# daclock-2_1.net
KiCad netlist of a schematic drawn in EAGLE
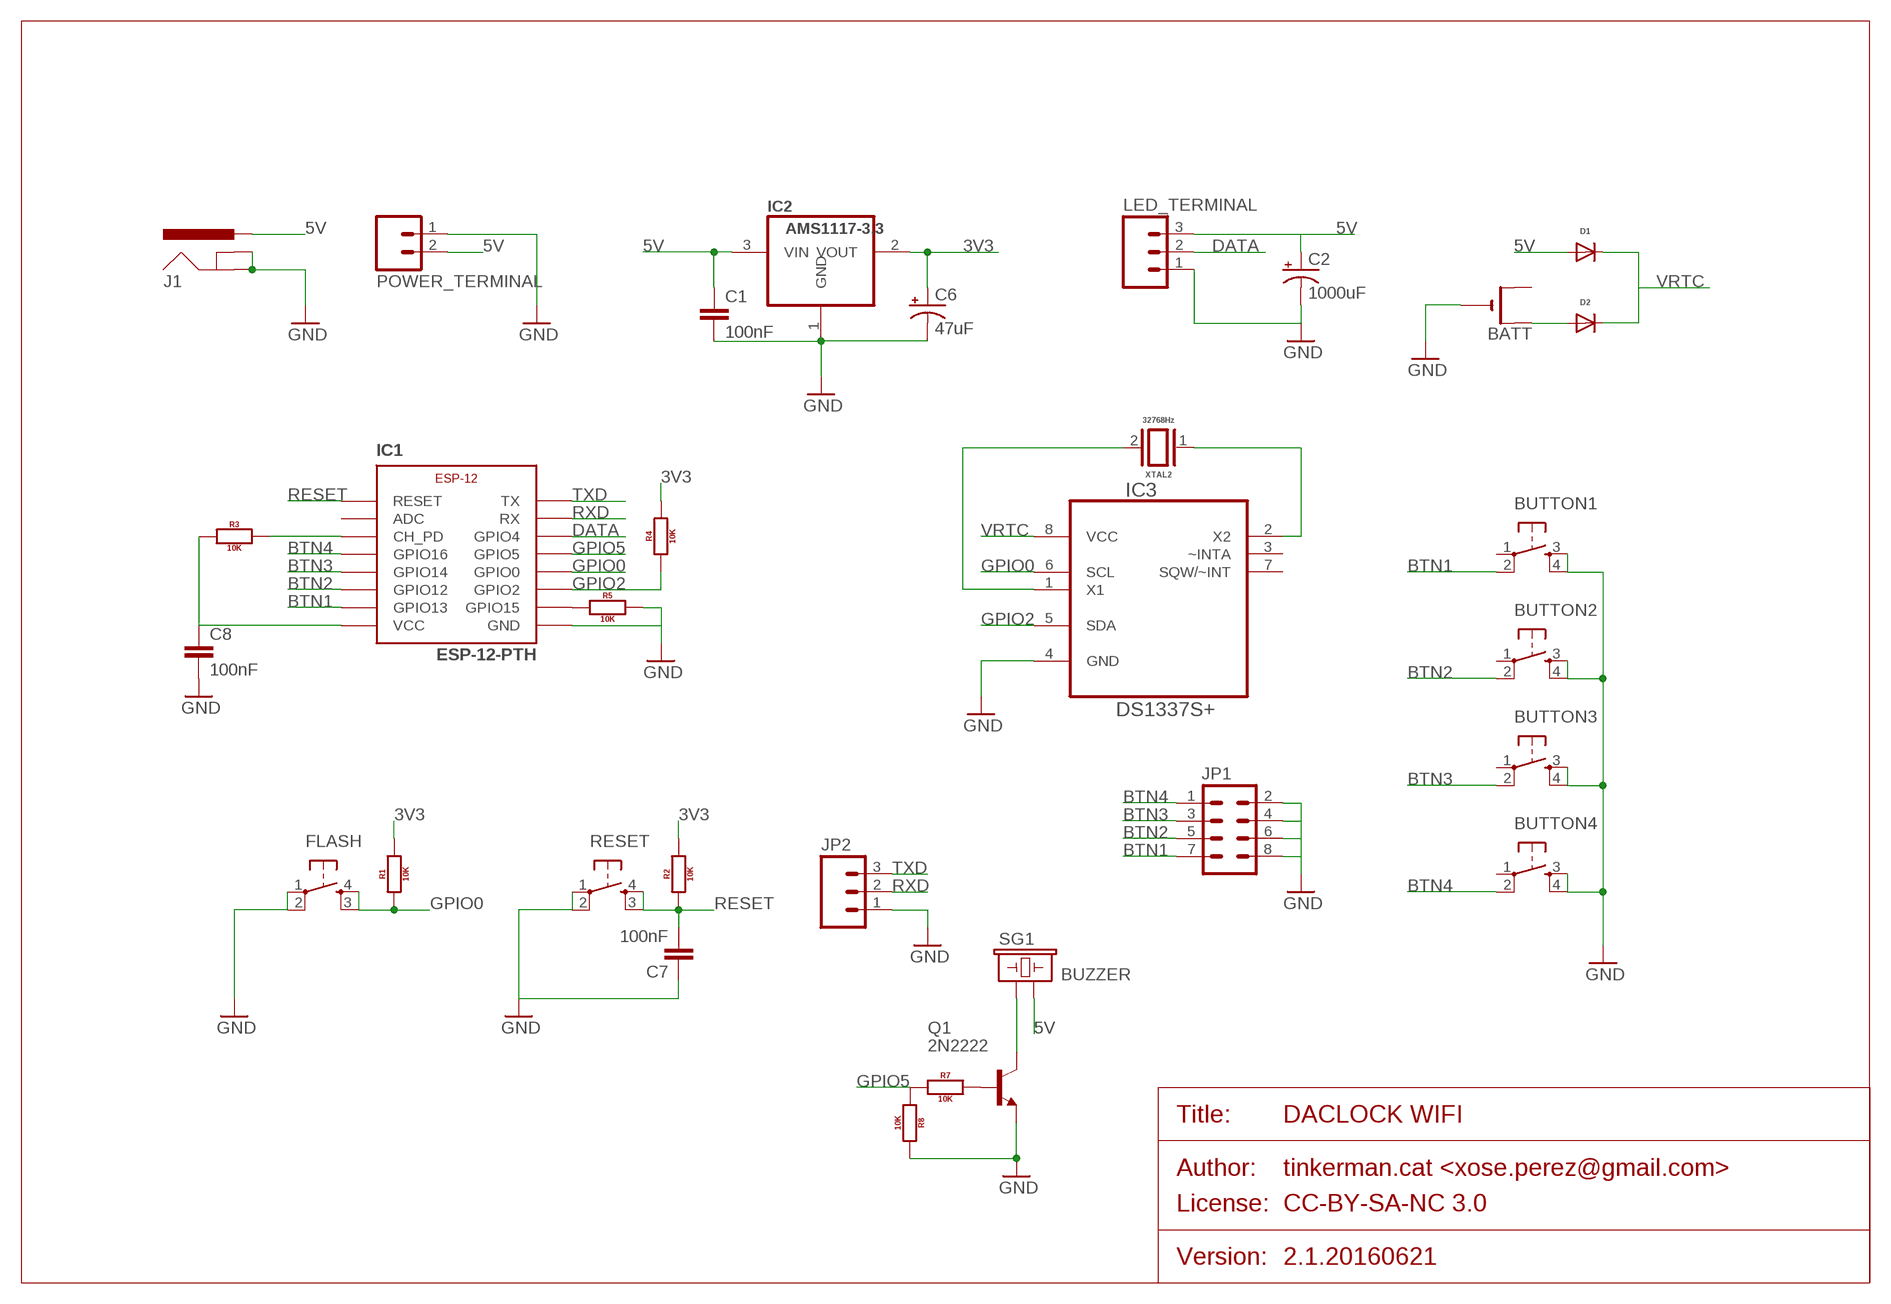
[diagram p0: schematic, sheet 1]

(export (version "E")
  (design (tool "Eeschema 10.0.6"))
  (components
    (comp (ref "BATT")
      (value "CR2032SMT")
      (footprint "eagle-import:CR2032-SMD")
      (libsource (lib "eagle-import") (part "CR2032SMT"))
    )
    (comp (ref "BUTTON1")
      (value "BTN1")
      (footprint "eagle-import:TACTILE-BUTTON")
      (libsource (lib "eagle-import") (part "TACTILE_BUTTON_PTH"))
    )
    (comp (ref "BUTTON2")
      (value "BTN2")
      (footprint "eagle-import:TACTILE-BUTTON")
      (libsource (lib "eagle-import") (part "TACTILE_BUTTON_PTH"))
    )
    (comp (ref "BUTTON3")
      (value "BTN3")
      (footprint "eagle-import:TACTILE-BUTTON")
      (libsource (lib "eagle-import") (part "TACTILE_BUTTON_PTH"))
    )
    (comp (ref "BUTTON4")
      (value "BTN4")
      (footprint "eagle-import:TACTILE-BUTTON")
      (libsource (lib "eagle-import") (part "TACTILE_BUTTON_PTH"))
    )
    (comp (ref "C1")
      (value "100nF")
      (footprint "eagle-import:C050-025X075")
      (libsource (lib "eagle-import") (part "C-EU050-025X075"))
    )
    (comp (ref "C2")
      (value "1000uF")
      (footprint "eagle-import:PANASONIC_G")
      (libsource (lib "eagle-import") (part "CAP_POLG"))
    )
    (comp (ref "C6")
      (value "47uF")
      (footprint "eagle-import:CPOL-RADIAL-10UF-25V")
      (libsource (lib "eagle-import") (part "CAP_POLPTH2"))
    )
    (comp (ref "C7")
      (value "100nF")
      (footprint "eagle-import:C050-025X075")
      (libsource (lib "eagle-import") (part "C-EU050-025X075"))
    )
    (comp (ref "C8")
      (value "100nF")
      (footprint "eagle-import:C050-025X075")
      (libsource (lib "eagle-import") (part "C-EU050-025X075"))
    )
    (comp (ref "D1")
      (value "DIODE-PTH4")
      (footprint "eagle-import:AXIAL-0.4-DIODE")
      (libsource (lib "eagle-import") (part "DIODE-PTH4"))
    )
    (comp (ref "D2")
      (value "DIODE-PTH4")
      (footprint "eagle-import:AXIAL-0.4-DIODE")
      (libsource (lib "eagle-import") (part "DIODE-PTH4"))
    )
    (comp (ref "FLASH")
      (value "TACTILE_BUTTON_SMD")
      (footprint "eagle-import:TACTILE-BUTTON-SMD")
      (libsource (lib "eagle-import") (part "TACTILE_BUTTON_SMD"))
    )
    (comp (ref "IC1")
      (value "ESP-12-PTH")
      (footprint "eagle-import:ESP-12-PTH")
      (libsource (lib "eagle-import") (part "ESP-12-PTH"))
    )
    (comp (ref "IC2")
      (value "AMS1117-3.3")
      (footprint "eagle-import:SOT223")
      (fields (field (name "MPN") "REG1117"))
      (libsource (lib "eagle-import") (part "REG1117"))
    )
    (comp (ref "IC3")
      (value "DS1337S+")
      (footprint "eagle-import:SOIC127P600X175-8N")
      (libsource (lib "eagle-import") (part "DS1337S+"))
    )
    (comp (ref "J1")
      (value "POWER_JACKPTH")
      (footprint "eagle-import:POWER_JACK_PTH")
      (libsource (lib "eagle-import") (part "POWER_JACKPTH"))
    )
    (comp (ref "JP1")
      (value "M04X2")
      (footprint "eagle-import:2X4")
      (libsource (lib "eagle-import") (part "M04X2"))
    )
    (comp (ref "JP2")
      (value "M03PTH")
      (footprint "eagle-import:1X03")
      (libsource (lib "eagle-import") (part "M03PTH"))
    )
    (comp (ref "LED_TERMINAL")
      (value "M03200MIL")
      (footprint "eagle-import:SCREWTERMINAL-200MIL-3")
      (libsource (lib "eagle-import") (part "M03200MIL"))
    )
    (comp (ref "POWER_TERMINAL")
      (value "M02200MIL")
      (footprint "eagle-import:SCREWTERMINAL-200MIL-2")
      (libsource (lib "eagle-import") (part "M02200MIL"))
    )
    (comp (ref "Q1")
      (value "2N2222")
      (footprint "eagle-import:TO92-EBC-OVAL")
      (libsource (lib "eagle-import") (part "2N2222"))
    )
    (comp (ref "R1")
      (value "10K")
      (footprint "eagle-import:AXIAL-0.4")
      (libsource (lib "eagle-import") (part "RESISTORPTH-400MIL"))
    )
    (comp (ref "R2")
      (value "10K")
      (footprint "eagle-import:AXIAL-0.4")
      (libsource (lib "eagle-import") (part "RESISTORPTH-400MIL"))
    )
    (comp (ref "R3")
      (value "10K")
      (footprint "eagle-import:AXIAL-0.4")
      (libsource (lib "eagle-import") (part "RESISTORPTH-400MIL"))
    )
    (comp (ref "R4")
      (value "10K")
      (footprint "eagle-import:AXIAL-0.4")
      (libsource (lib "eagle-import") (part "RESISTORPTH-400MIL"))
    )
    (comp (ref "R5")
      (value "10K")
      (footprint "eagle-import:AXIAL-0.4")
      (libsource (lib "eagle-import") (part "RESISTORPTH-400MIL"))
    )
    (comp (ref "R7")
      (value "10K")
      (footprint "eagle-import:AXIAL-0.4")
      (libsource (lib "eagle-import") (part "RESISTORPTH-400MIL"))
    )
    (comp (ref "R8")
      (value "10K")
      (footprint "eagle-import:AXIAL-0.4")
      (libsource (lib "eagle-import") (part "RESISTORPTH-400MIL"))
    )
    (comp (ref "RESET")
      (value "TACTILE_BUTTON_SMD")
      (footprint "eagle-import:TACTILE-BUTTON-SMD")
      (libsource (lib "eagle-import") (part "TACTILE_BUTTON_SMD"))
    )
    (comp (ref "SG1")
      (value "BUZZER")
      (footprint "eagle-import:BUZZER-12MM")
      (libsource (lib "eagle-import") (part "BUZZERPTH"))
    )
    (comp (ref "XTAL2")
      (value "32768Hz")
      (footprint "eagle-import:TC38H")
      (libsource (lib "eagle-import") (part "CRYSTAL_TC38H"))
    )
  )
  (nets
    (net (code "1") (name "/3V3") (class "Default")
      (node (ref "C6") (pin "1") (pinfunction "+_1") (pintype "passive"))
      (node (ref "C8") (pin "1") (pinfunction "1_1") (pintype "passive"))
      (node (ref "IC1") (pin "VCC") (pinfunction "VCC_VCC") (pintype "bidirectional"))
      (node (ref "IC2") (pin "2") (pinfunction "VOUT_2") (pintype "output"))
      (node (ref "R1") (pin "P$2") (pinfunction "2_P$2") (pintype "passive"))
      (node (ref "R2") (pin "P$2") (pinfunction "2_P$2") (pintype "passive"))
      (node (ref "R3") (pin "P$1") (pinfunction "1_P$1") (pintype "passive"))
      (node (ref "R4") (pin "P$2") (pinfunction "2_P$2") (pintype "passive"))
    )
    (net (code "2") (name "/5V") (class "Default")
      (node (ref "C1") (pin "1") (pinfunction "1_1") (pintype "passive"))
      (node (ref "C2") (pin "+") (pinfunction "+_+") (pintype "passive"))
      (node (ref "D1") (pin "A") (pinfunction "A_A") (pintype "passive"))
      (node (ref "IC2") (pin "3") (pinfunction "VIN_3") (pintype "input"))
      (node (ref "J1") (pin "PWR") (pinfunction "PWR_PWR") (pintype "bidirectional"))
      (node (ref "LED_TERMINAL") (pin "3") (pinfunction "3_3") (pintype "passive"))
      (node (ref "POWER_TERMINAL") (pin "2") (pinfunction "2_2") (pintype "passive"))
      (node (ref "SG1") (pin "-") (pinfunction "2_-") (pintype "passive"))
    )
    (net (code "3") (name "/BTN1") (class "Default")
      (node (ref "BUTTON1") (pin "2") (pinfunction "SWB1_2") (pintype "passive"))
      (node (ref "IC1") (pin "GPIO13") (pinfunction "GPIO13_GPIO13") (pintype "bidirectional"))
      (node (ref "JP1") (pin "7") (pinfunction "7_7") (pintype "passive"))
    )
    (net (code "4") (name "/BTN2") (class "Default")
      (node (ref "BUTTON2") (pin "2") (pinfunction "SWB1_2") (pintype "passive"))
      (node (ref "IC1") (pin "GPIO12") (pinfunction "GPIO12_GPIO12") (pintype "bidirectional"))
      (node (ref "JP1") (pin "5") (pinfunction "5_5") (pintype "passive"))
    )
    (net (code "5") (name "/BTN3") (class "Default")
      (node (ref "BUTTON3") (pin "2") (pinfunction "SWB1_2") (pintype "passive"))
      (node (ref "IC1") (pin "GPIO14") (pinfunction "GPIO14_GPIO14") (pintype "bidirectional"))
      (node (ref "JP1") (pin "3") (pinfunction "3_3") (pintype "passive"))
    )
    (net (code "6") (name "/BTN4") (class "Default")
      (node (ref "BUTTON4") (pin "2") (pinfunction "SWB1_2") (pintype "passive"))
      (node (ref "IC1") (pin "GPIO16") (pinfunction "GPIO16_GPIO16") (pintype "bidirectional"))
      (node (ref "JP1") (pin "1") (pinfunction "1_1") (pintype "passive"))
    )
    (net (code "7") (name "/DATA") (class "Default")
      (node (ref "IC1") (pin "GPIO4") (pinfunction "GPIO4_GPIO4") (pintype "bidirectional"))
      (node (ref "LED_TERMINAL") (pin "2") (pinfunction "2_2") (pintype "passive"))
    )
    (net (code "8") (name "/GPIO0") (class "Default")
      (node (ref "FLASH") (pin "3") (pinfunction "SWB2_3") (pintype "passive"))
      (node (ref "FLASH") (pin "4") (pinfunction "SWA2_4") (pintype "passive"))
      (node (ref "IC1") (pin "GPIO0") (pinfunction "GPIO0_GPIO0") (pintype "bidirectional"))
      (node (ref "IC3") (pin "6") (pinfunction "SCL_6") (pintype "input"))
      (node (ref "R1") (pin "P$1") (pinfunction "1_P$1") (pintype "passive"))
    )
    (net (code "9") (name "/GPIO2") (class "Default")
      (node (ref "IC1") (pin "GPIO2") (pinfunction "GPIO2_GPIO2") (pintype "bidirectional"))
      (node (ref "IC3") (pin "5") (pinfunction "SDA_5") (pintype "bidirectional"))
      (node (ref "R4") (pin "P$1") (pinfunction "1_P$1") (pintype "passive"))
    )
    (net (code "10") (name "/GPIO5") (class "Default")
      (node (ref "IC1") (pin "GPIO5") (pinfunction "GPIO5_GPIO5") (pintype "bidirectional"))
      (node (ref "R7") (pin "P$1") (pinfunction "1_P$1") (pintype "passive"))
      (node (ref "R8") (pin "P$1") (pinfunction "1_P$1") (pintype "passive"))
    )
    (net (code "11") (name "/RESET") (class "Default")
      (node (ref "C7") (pin "2") (pinfunction "2_2") (pintype "passive"))
      (node (ref "IC1") (pin "RESET") (pinfunction "RESET_RESET") (pintype "bidirectional"))
      (node (ref "R2") (pin "P$1") (pinfunction "1_P$1") (pintype "passive"))
      (node (ref "RESET") (pin "3") (pinfunction "SWB2_3") (pintype "passive"))
      (node (ref "RESET") (pin "4") (pinfunction "SWA2_4") (pintype "passive"))
    )
    (net (code "12") (name "/RXD") (class "Default")
      (node (ref "IC1") (pin "RX") (pinfunction "RX_RX") (pintype "bidirectional"))
      (node (ref "JP2") (pin "2") (pinfunction "2_2") (pintype "passive"))
    )
    (net (code "13") (name "/TXD") (class "Default")
      (node (ref "IC1") (pin "TX") (pinfunction "TX_TX") (pintype "bidirectional"))
      (node (ref "JP2") (pin "3") (pinfunction "3_3") (pintype "passive"))
    )
    (net (code "14") (name "/VRTC") (class "Default")
      (node (ref "D1") (pin "C") (pinfunction "C_C") (pintype "passive"))
      (node (ref "D2") (pin "C") (pinfunction "C_C") (pintype "passive"))
      (node (ref "IC3") (pin "8") (pinfunction "VCC_8") (pintype "power_in"))
    )
    (net (code "15") (name "GND") (class "Default")
      (node (ref "BATT") (pin "-") (pinfunction "-_-") (pintype "passive"))
      (node (ref "BUTTON1") (pin "3") (pinfunction "SWA2_3") (pintype "passive"))
      (node (ref "BUTTON1") (pin "4") (pinfunction "SWB2_4") (pintype "passive"))
      (node (ref "BUTTON2") (pin "3") (pinfunction "SWA2_3") (pintype "passive"))
      (node (ref "BUTTON2") (pin "4") (pinfunction "SWB2_4") (pintype "passive"))
      (node (ref "BUTTON3") (pin "3") (pinfunction "SWA2_3") (pintype "passive"))
      (node (ref "BUTTON3") (pin "4") (pinfunction "SWB2_4") (pintype "passive"))
      (node (ref "BUTTON4") (pin "3") (pinfunction "SWA2_3") (pintype "passive"))
      (node (ref "BUTTON4") (pin "4") (pinfunction "SWB2_4") (pintype "passive"))
      (node (ref "C1") (pin "2") (pinfunction "2_2") (pintype "passive"))
      (node (ref "C2") (pin "-") (pinfunction "-_-") (pintype "passive"))
      (node (ref "C6") (pin "2") (pinfunction "-_2") (pintype "passive"))
      (node (ref "C7") (pin "1") (pinfunction "1_1") (pintype "passive"))
      (node (ref "C8") (pin "2") (pinfunction "2_2") (pintype "passive"))
      (node (ref "FLASH") (pin "1") (pinfunction "SWA1_1") (pintype "passive"))
      (node (ref "FLASH") (pin "2") (pinfunction "SWB1_2") (pintype "passive"))
      (node (ref "IC1") (pin "GND") (pinfunction "GND_GND") (pintype "bidirectional"))
      (node (ref "IC2") (pin "1") (pinfunction "GND_1") (pintype "power_in"))
      (node (ref "IC3") (pin "4") (pinfunction "GND_4") (pintype "passive"))
      (node (ref "J1") (pin "GND") (pinfunction "GND_GND") (pintype "bidirectional"))
      (node (ref "J1") (pin "GNDBREAK") (pinfunction "GNDBREAK_GNDBREAK") (pintype "bidirectional"))
      (node (ref "JP1") (pin "2") (pinfunction "2_2") (pintype "passive"))
      (node (ref "JP1") (pin "4") (pinfunction "4_4") (pintype "passive"))
      (node (ref "JP1") (pin "6") (pinfunction "6_6") (pintype "passive"))
      (node (ref "JP1") (pin "8") (pinfunction "8_8") (pintype "passive"))
      (node (ref "JP2") (pin "1") (pinfunction "1_1") (pintype "passive"))
      (node (ref "LED_TERMINAL") (pin "1") (pinfunction "1_1") (pintype "passive"))
      (node (ref "POWER_TERMINAL") (pin "1") (pinfunction "1_1") (pintype "passive"))
      (node (ref "Q1") (pin "E") (pinfunction "E_E") (pintype "passive"))
      (node (ref "R5") (pin "P$2") (pinfunction "2_P$2") (pintype "passive"))
      (node (ref "R8") (pin "P$2") (pinfunction "2_P$2") (pintype "passive"))
      (node (ref "RESET") (pin "1") (pinfunction "SWA1_1") (pintype "passive"))
      (node (ref "RESET") (pin "2") (pinfunction "SWB1_2") (pintype "passive"))
    )
    (net (code "16") (name "Net-(BATT-+)") (class "Default")
      (node (ref "BATT") (pin "+$1") (pinfunction "+_+$1") (pintype "passive"))
      (node (ref "D2") (pin "A") (pinfunction "A_A") (pintype "passive"))
    )
    (net (code "17") (name "Net-(IC3-X1)") (class "Default")
      (node (ref "IC3") (pin "1") (pinfunction "X1_1") (pintype "input"))
      (node (ref "XTAL2") (pin "2") (pinfunction "2_2") (pintype "passive"))
    )
    (net (code "18") (name "Net-(IC3-X2)") (class "Default")
      (node (ref "IC3") (pin "2") (pinfunction "X2_2") (pintype "passive"))
      (node (ref "XTAL2") (pin "1") (pinfunction "1_1") (pintype "passive"))
    )
    (net (code "19") (name "Net-(R3-2)") (class "Default")
      (node (ref "IC1") (pin "CH_PD") (pinfunction "CH_PD_CH_PD") (pintype "bidirectional"))
      (node (ref "R3") (pin "P$2") (pinfunction "2_P$2") (pintype "passive"))
    )
    (net (code "20") (name "Net-(R5-1)") (class "Default")
      (node (ref "IC1") (pin "GPIO15") (pinfunction "GPIO15_GPIO15") (pintype "bidirectional"))
      (node (ref "R5") (pin "P$1") (pinfunction "1_P$1") (pintype "passive"))
    )
    (net (code "21") (name "Net-(R7-2)") (class "Default")
      (node (ref "Q1") (pin "B") (pinfunction "B_B") (pintype "passive"))
      (node (ref "R7") (pin "P$2") (pinfunction "2_P$2") (pintype "passive"))
    )
    (net (code "22") (name "Net-(SG1-1)") (class "Default")
      (node (ref "Q1") (pin "C") (pinfunction "C_C") (pintype "passive"))
      (node (ref "SG1") (pin "+") (pinfunction "1_+") (pintype "passive"))
    )
    (net (code "23") (name "unconnected-(BATT-+1-Pad+$2)") (class "Default")
      (node (ref "BATT") (pin "+$2") (pinfunction "+1_+$2") (pintype "passive"))
    )
    (net (code "24") (name "unconnected-(BUTTON1-SWA1-Pad1)") (class "Default")
      (node (ref "BUTTON1") (pin "1") (pinfunction "SWA1_1") (pintype "passive"))
    )
    (net (code "25") (name "unconnected-(BUTTON2-SWA1-Pad1)") (class "Default")
      (node (ref "BUTTON2") (pin "1") (pinfunction "SWA1_1") (pintype "passive"))
    )
    (net (code "26") (name "unconnected-(BUTTON3-SWA1-Pad1)") (class "Default")
      (node (ref "BUTTON3") (pin "1") (pinfunction "SWA1_1") (pintype "passive"))
    )
    (net (code "27") (name "unconnected-(BUTTON4-SWA1-Pad1)") (class "Default")
      (node (ref "BUTTON4") (pin "1") (pinfunction "SWA1_1") (pintype "passive"))
    )
    (net (code "28") (name "unconnected-(IC1-PadADC)") (class "Default")
      (node (ref "IC1") (pin "ADC") (pinfunction "ADC_ADC") (pintype "bidirectional"))
    )
    (net (code "29") (name "unconnected-(IC3-SQW{slash}~{INT}-Pad7)") (class "Default")
      (node (ref "IC3") (pin "7") (pinfunction "SQW/~{INT}_7") (pintype "output"))
    )
    (net (code "30") (name "unconnected-(IC3-~{INTA}-Pad3)") (class "Default")
      (node (ref "IC3") (pin "3") (pinfunction "~{INTA}_3") (pintype "output"))
    )
  )
)
